# usb_otg.net
KiCad netlist of a schematic drawn in Altium Designer
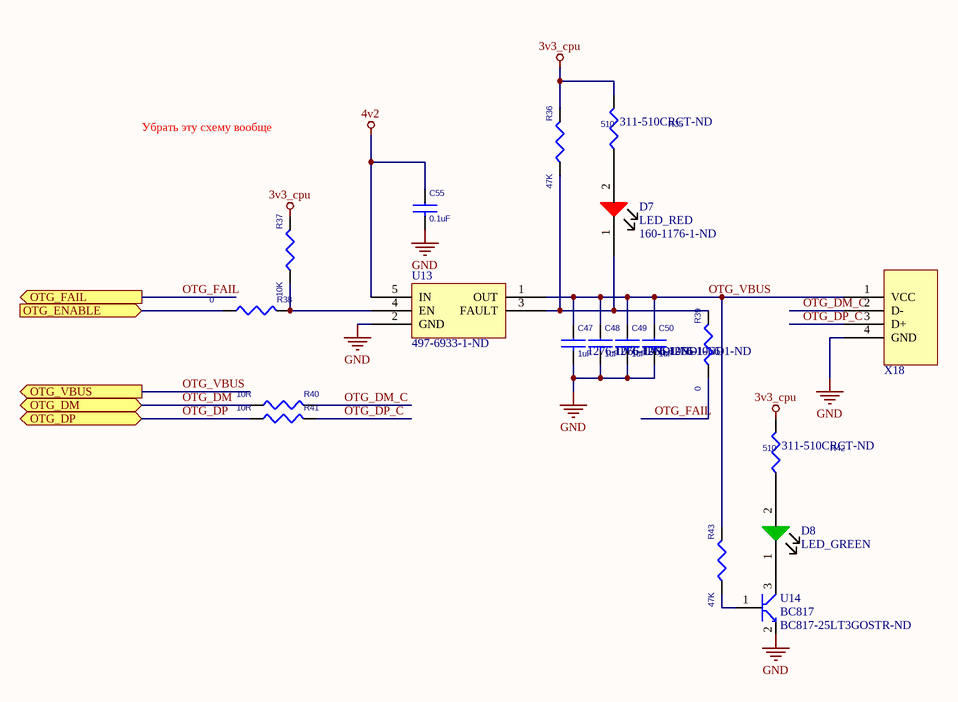
[diagram p0: usb_otg.SchDoc]

(export (version "E")
  (design (tool "Eeschema 10.0.6"))
  (components
    (comp (ref "C47")
      (value "1uF")
      (footprint "CAPC2012X09M")
      (description "MLCC; 1uF; 25V; X7R; ±10%; SMD; 0805;")
      (fields (field (name "SUPPLIER PART NUMBER 1") "1276-1066-1-ND"))
      (libsource (lib "Capacitors") (part "CAP_SMD_1uF_10%"))
    )
    (comp (ref "C48")
      (value "1uF")
      (footprint "CAPC2012X09M")
      (description "MLCC; 1uF; 25V; X7R; ±10%; SMD; 0805;")
      (fields (field (name "SUPPLIER PART NUMBER 1") "1276-1066-1-ND"))
      (libsource (lib "Capacitors") (part "CAP_SMD_1uF_10%"))
    )
    (comp (ref "C49")
      (value "1uF")
      (footprint "CAPC2012X09M")
      (description "MLCC; 1uF; 25V; X7R; ±10%; SMD; 0805;")
      (fields (field (name "SUPPLIER PART NUMBER 1") "1276-1066-1-ND"))
      (libsource (lib "Capacitors") (part "CAP_SMD_1uF_10%"))
    )
    (comp (ref "C50")
      (value "1uF")
      (footprint "CAPC2012X09M")
      (description "MLCC; 1uF; 25V; X7R; ±10%; SMD; 0805;")
      (fields (field (name "SUPPLIER PART NUMBER 1") "1276-1066-1-ND"))
      (libsource (lib "Capacitors") (part "CAP_SMD_1uF_10%"))
    )
    (comp (ref "C55")
      (value "0.1uF")
      (footprint "CAPC2012X09M")
      (description "CAP CER 0.1UF 25V 10% X7R 0805")
      (libsource (lib "Capacitors") (part "CAP_SMD_0.1UF_10%"))
    )
    (comp (ref "D7")
      (value "LED_RED")
      (footprint "DIOC2012X11N")
      (fields (field (name "SUPPLIER PART NUMBER 1") "160-1176-1-ND"))
      (libsource (lib "Passive") (part "LED_RED"))
    )
    (comp (ref "D8")
      (value "LED_GREEN")
      (footprint "DIOC2012X11N")
      (libsource (lib "Passive") (part "LED_GREEN"))
    )
    (comp (ref "R35")
      (value "510")
      (footprint "RESC2013X06M")
      (description "RES - 510 OHM, 5%, 1/8W, 0805 SMD")
      (fields (field (name "SUPPLIER PART NUMBER 1") "311-510CRCT-ND"))
      (libsource (lib "Resistors") (part "RES_SMD_510_5%"))
    )
    (comp (ref "R36")
      (value "47K")
      (footprint "RESC2013X06M")
      (description "RES 47K OHM 1/8W 1% 0805")
      (libsource (lib "Resistors") (part "RES_SMD_47K_1%"))
    )
    (comp (ref "R37")
      (value "10K")
      (footprint "RESC2013X06M")
      (description "RES 10K OHM 1/8W 5% 0805 SMD")
      (libsource (lib "Resistors") (part "RES_SMD_10K_5%"))
    )
    (comp (ref "R38")
      (value "0")
      (footprint "RESC2013X06M")
      (description "RES 0.0 OHM 1/8W JUMP 0805 SMD")
      (libsource (lib "Resistors") (part "RES_SMD_0"))
    )
    (comp (ref "R39")
      (value "0")
      (footprint "RESC2013X06M")
      (description "RES 0.0 OHM 1/8W JUMP 0805 SMD")
      (libsource (lib "Resistors") (part "RES_SMD_0"))
    )
    (comp (ref "R40")
      (value "10R")
      (footprint "RESC2013X06M")
      (description "RES 10 OHM 1/8W 1% 0805 SMD")
      (libsource (lib "Resistors") (part "RES_SMD_10R_5%"))
    )
    (comp (ref "R41")
      (value "10R")
      (footprint "RESC2013X06M")
      (description "RES 10 OHM 1/8W 1% 0805 SMD")
      (libsource (lib "Resistors") (part "RES_SMD_10R_5%"))
    )
    (comp (ref "R42")
      (value "510")
      (footprint "RESC2013X06M")
      (description "RES - 510 OHM, 5%, 1/8W, 0805 SMD")
      (fields (field (name "SUPPLIER PART NUMBER 1") "311-510CRCT-ND"))
      (libsource (lib "Resistors") (part "RES_SMD_510_5%"))
    )
    (comp (ref "R43")
      (value "47K")
      (footprint "RESC2013X06M")
      (description "RES 47K OHM 1/8W 1% 0805")
      (libsource (lib "Resistors") (part "RES_SMD_47K_1%"))
    )
    (comp (ref "U13")
      (value "STMPS2141STR")
      (footprint "SOT95P280X145-5N")
      (fields (field (name "SUPPLIER PART NUMBER 1") "497-6933-1-ND"))
      (libsource (lib "TruthEar") (part "STMPS2141STR"))
    )
    (comp (ref "U14")
      (value "BC817")
      (footprint "SOT95P237X111-3N_SOT-23")
      (fields (field (name "SUPPLIER PART NUMBER 1") "BC817-25LT3GOSTR-ND"))
      (libsource (lib "TruthEar") (part "BC817"))
    )
    (comp (ref "X18")
      (value "743941-da-01")
      (footprint "USB-A")
      (libsource (lib "Connectors") (part "USB-A-FEMALE"))
    )
  )
  (nets
    (net (code "1") (name "/OTG_DM") (class "Default")
      (node (ref "R40") (pin "1") (pinfunction "1_1") (pintype "passive"))
    )
    (net (code "2") (name "/OTG_DM_C") (class "Default")
      (node (ref "R40") (pin "2") (pinfunction "2_2") (pintype "passive"))
      (node (ref "X18") (pin "2") (pinfunction "D-_2") (pintype "power_in"))
    )
    (net (code "3") (name "/OTG_DP") (class "Default")
      (node (ref "R41") (pin "1") (pinfunction "1_1") (pintype "passive"))
    )
    (net (code "4") (name "/OTG_DP_C") (class "Default")
      (node (ref "R41") (pin "2") (pinfunction "2_2") (pintype "passive"))
      (node (ref "X18") (pin "3") (pinfunction "D+_3") (pintype "power_in"))
    )
    (net (code "5") (name "/OTG_ENABLE") (class "Default")
      (node (ref "R38") (pin "1") (pinfunction "1_1") (pintype "passive"))
    )
    (net (code "6") (name "/OTG_FAIL") (class "Default")
      (node (ref "R39") (pin "1") (pinfunction "1_1") (pintype "passive"))
    )
    (net (code "7") (name "/OTG_VBUS") (class "Default")
      (node (ref "C47") (pin "1") (pinfunction "1_1") (pintype "passive"))
      (node (ref "C48") (pin "1") (pinfunction "1_1") (pintype "passive"))
      (node (ref "C49") (pin "1") (pinfunction "1_1") (pintype "passive"))
      (node (ref "C50") (pin "1") (pinfunction "1_1") (pintype "passive"))
      (node (ref "R43") (pin "2") (pinfunction "2_2") (pintype "passive"))
      (node (ref "U13") (pin "1") (pinfunction "OUT_1") (pintype "power_in"))
      (node (ref "X18") (pin "1") (pinfunction "VCC_1") (pintype "power_in"))
    )
    (net (code "8") (name "3v3_cpu") (class "Default")
      (node (ref "R35") (pin "2") (pinfunction "2_2") (pintype "passive"))
      (node (ref "R36") (pin "2") (pinfunction "2_2") (pintype "passive"))
      (node (ref "R37") (pin "2") (pinfunction "2_2") (pintype "passive"))
      (node (ref "R42") (pin "2") (pinfunction "2_2") (pintype "passive"))
    )
    (net (code "9") (name "4v2") (class "Default")
      (node (ref "C55") (pin "1") (pinfunction "1_1") (pintype "passive"))
      (node (ref "U13") (pin "5") (pinfunction "IN_5") (pintype "power_in"))
    )
    (net (code "10") (name "GND") (class "Default")
      (node (ref "C47") (pin "2") (pinfunction "2_2") (pintype "passive"))
      (node (ref "C48") (pin "2") (pinfunction "2_2") (pintype "passive"))
      (node (ref "C49") (pin "2") (pinfunction "2_2") (pintype "passive"))
      (node (ref "C50") (pin "2") (pinfunction "2_2") (pintype "passive"))
      (node (ref "C55") (pin "2") (pinfunction "2_2") (pintype "passive"))
      (node (ref "U13") (pin "2") (pinfunction "GND_2") (pintype "power_in"))
      (node (ref "U14") (pin "2") (pinfunction "E_2") (pintype "passive"))
      (node (ref "X18") (pin "4") (pinfunction "GND_4") (pintype "power_in"))
    )
    (net (code "11") (name "Net-(D7-A)") (class "Default")
      (node (ref "D7") (pin "2") (pinfunction "A_2") (pintype "passive"))
      (node (ref "R35") (pin "1") (pinfunction "1_1") (pintype "passive"))
    )
    (net (code "12") (name "Net-(D7-C)") (class "Default")
      (node (ref "D7") (pin "1") (pinfunction "C_1") (pintype "passive"))
      (node (ref "R36") (pin "1") (pinfunction "1_1") (pintype "passive"))
      (node (ref "R39") (pin "2") (pinfunction "2_2") (pintype "passive"))
      (node (ref "U13") (pin "3") (pinfunction "FAULT_3") (pintype "power_in"))
    )
    (net (code "13") (name "Net-(D8-A)") (class "Default")
      (node (ref "D8") (pin "2") (pinfunction "A_2") (pintype "passive"))
      (node (ref "R42") (pin "1") (pinfunction "1_1") (pintype "passive"))
    )
    (net (code "14") (name "Net-(D8-C)") (class "Default")
      (node (ref "D8") (pin "1") (pinfunction "C_1") (pintype "passive"))
      (node (ref "U14") (pin "3") (pinfunction "C_3") (pintype "passive"))
    )
    (net (code "15") (name "Net-(U13-EN)") (class "Default")
      (node (ref "R37") (pin "1") (pinfunction "1_1") (pintype "passive"))
      (node (ref "R38") (pin "2") (pinfunction "2_2") (pintype "passive"))
      (node (ref "U13") (pin "4") (pinfunction "EN_4") (pintype "power_in"))
    )
    (net (code "16") (name "Net-(U14-B)") (class "Default")
      (node (ref "R43") (pin "1") (pinfunction "1_1") (pintype "passive"))
      (node (ref "U14") (pin "1") (pinfunction "B_1") (pintype "passive"))
    )
  )
)
